# DDR4_SODIMM_Arria10.net
KiCad netlist of a schematic drawn in Altium Designer
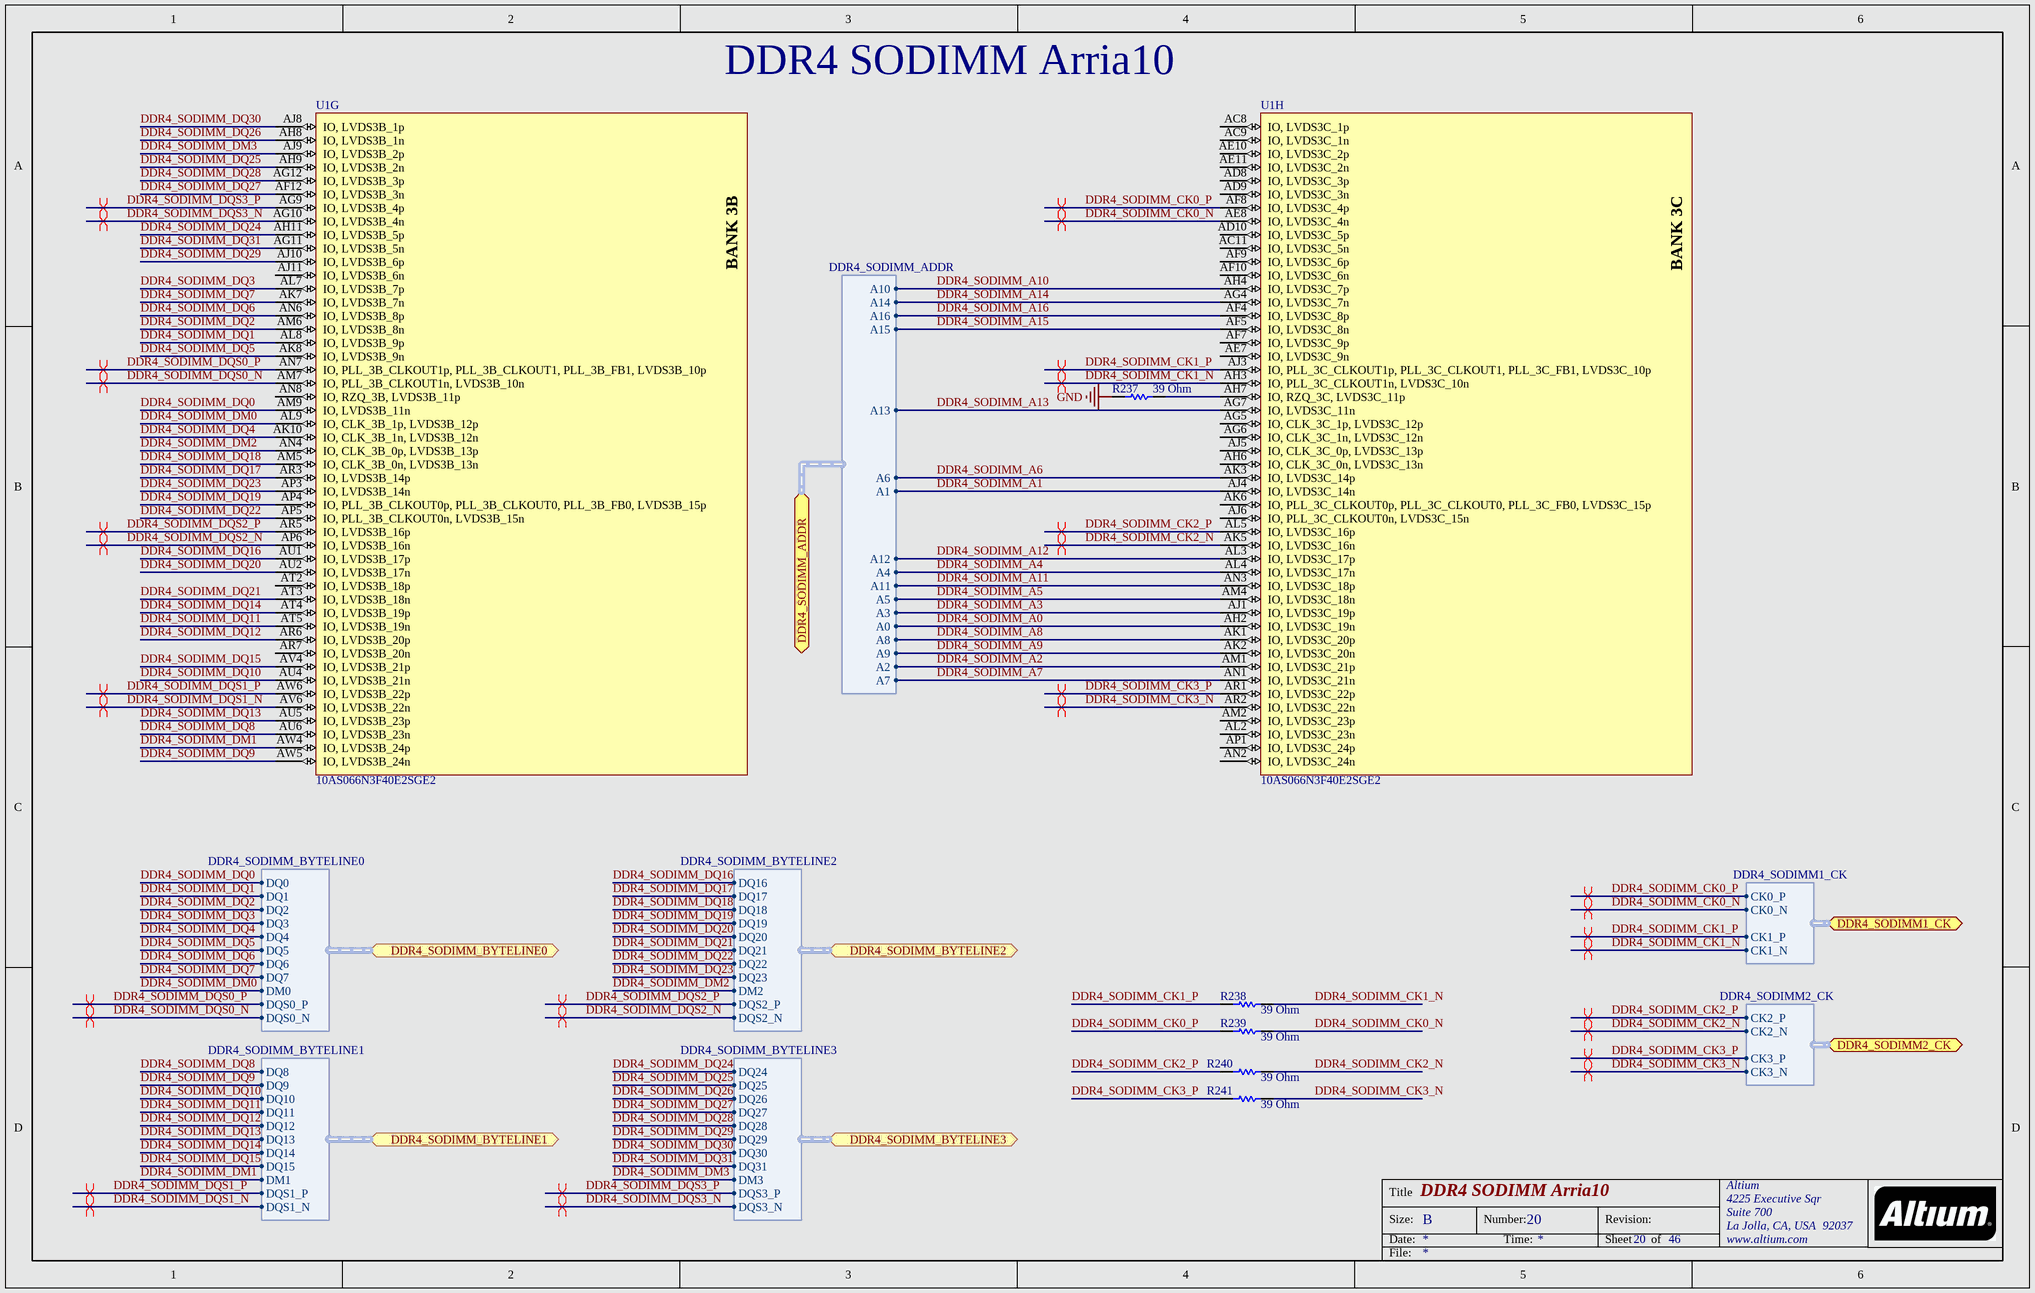
[diagram p0: DDR4_SODIMM_Arria10.SchDoc]

(export (version "E")
  (design (tool "Eeschema 10.0.6"))
  (components
    (comp (ref "R237")
      (value "RC0402JR-0739RL")
      (footprint "RESC1005X40X25NL5T10")
      (description "Chip Resistor, 39 Ohm, +/- 5%, 0.063 W, -55 to 155 degC, 0402 (1005 Metric), RoHS, Tape and Reel")
      (fields (field (name "TOLERANCE") "5%") (field (name "RESISTANCE") "39 Ohm"))
      (libsource (lib "Altium Content Vault") (part "CMP-2002-07994-2"))
    )
    (comp (ref "R238")
      (value "RC0402JR-0739RL")
      (footprint "RESC1005X40X25NL5T10")
      (description "Chip Resistor, 39 Ohm, +/- 5%, 0.063 W, -55 to 155 degC, 0402 (1005 Metric), RoHS, Tape and Reel")
      (fields (field (name "TOLERANCE") "5%") (field (name "RESISTANCE") "39 Ohm"))
      (libsource (lib "Altium Content Vault") (part "CMP-2002-07994-2"))
    )
    (comp (ref "R239")
      (value "RC0402JR-0739RL")
      (footprint "RESC1005X40X25NL5T10")
      (description "Chip Resistor, 39 Ohm, +/- 5%, 0.063 W, -55 to 155 degC, 0402 (1005 Metric), RoHS, Tape and Reel")
      (fields (field (name "TOLERANCE") "5%") (field (name "RESISTANCE") "39 Ohm"))
      (libsource (lib "Altium Content Vault") (part "CMP-2002-07994-2"))
    )
    (comp (ref "R240")
      (value "RC0402JR-0739RL")
      (footprint "RESC1005X40X25NL5T10")
      (description "Chip Resistor, 39 Ohm, +/- 5%, 0.063 W, -55 to 155 degC, 0402 (1005 Metric), RoHS, Tape and Reel")
      (fields (field (name "TOLERANCE") "5%") (field (name "RESISTANCE") "39 Ohm"))
      (libsource (lib "Altium Content Vault") (part "CMP-2002-07994-2"))
    )
    (comp (ref "R241")
      (value "RC0402JR-0739RL")
      (footprint "RESC1005X40X25NL5T10")
      (description "Chip Resistor, 39 Ohm, +/- 5%, 0.063 W, -55 to 155 degC, 0402 (1005 Metric), RoHS, Tape and Reel")
      (fields (field (name "TOLERANCE") "5%") (field (name "RESISTANCE") "39 Ohm"))
      (libsource (lib "Altium Content Vault") (part "CMP-2002-07994-2"))
    )
    (comp (ref "U1")
      (value "10AS066N3F40E2SGE2")
      (footprint "ALTR-FBGA1517_A-350")
      (libsource (lib "Altium Content Vault") (part "ALTR-10AS066NF40-FBGA1517"))
    )
  )
  (nets
    (net (code "8") (name "/DDR4_SODIMM_A0") (class "Default")
      (node (ref "U1") (pin "AH2") (pinfunction "IO,_LVDS3C_19n_AH2") (pintype "bidirectional"))
    )
    (net (code "9") (name "/DDR4_SODIMM_A1") (class "Default")
      (node (ref "U1") (pin "AJ4") (pinfunction "IO,_LVDS3C_14n_AJ4") (pintype "bidirectional"))
    )
    (net (code "10") (name "/DDR4_SODIMM_A2") (class "Default")
      (node (ref "U1") (pin "AM1") (pinfunction "IO,_LVDS3C_21p_AM1") (pintype "bidirectional"))
    )
    (net (code "11") (name "/DDR4_SODIMM_A3") (class "Default")
      (node (ref "U1") (pin "AJ1") (pinfunction "IO,_LVDS3C_19p_AJ1") (pintype "bidirectional"))
    )
    (net (code "12") (name "/DDR4_SODIMM_A4") (class "Default")
      (node (ref "U1") (pin "AL4") (pinfunction "IO,_LVDS3C_17n_AL4") (pintype "bidirectional"))
    )
    (net (code "13") (name "/DDR4_SODIMM_A5") (class "Default")
      (node (ref "U1") (pin "AM4") (pinfunction "IO,_LVDS3C_18n_AM4") (pintype "bidirectional"))
    )
    (net (code "14") (name "/DDR4_SODIMM_A6") (class "Default")
      (node (ref "U1") (pin "AK3") (pinfunction "IO,_LVDS3C_14p_AK3") (pintype "bidirectional"))
    )
    (net (code "15") (name "/DDR4_SODIMM_A7") (class "Default")
      (node (ref "U1") (pin "AN1") (pinfunction "IO,_LVDS3C_21n_AN1") (pintype "bidirectional"))
    )
    (net (code "16") (name "/DDR4_SODIMM_A8") (class "Default")
      (node (ref "U1") (pin "AK1") (pinfunction "IO,_LVDS3C_20p_AK1") (pintype "bidirectional"))
    )
    (net (code "17") (name "/DDR4_SODIMM_A9") (class "Default")
      (node (ref "U1") (pin "AK2") (pinfunction "IO,_LVDS3C_20n_AK2") (pintype "bidirectional"))
    )
    (net (code "18") (name "/DDR4_SODIMM_A10") (class "Default")
      (node (ref "U1") (pin "AH4") (pinfunction "IO,_LVDS3C_7p_AH4") (pintype "bidirectional"))
    )
    (net (code "19") (name "/DDR4_SODIMM_A11") (class "Default")
      (node (ref "U1") (pin "AN3") (pinfunction "IO,_LVDS3C_18p_AN3") (pintype "bidirectional"))
    )
    (net (code "20") (name "/DDR4_SODIMM_A12") (class "Default")
      (node (ref "U1") (pin "AL3") (pinfunction "IO,_LVDS3C_17p_AL3") (pintype "bidirectional"))
    )
    (net (code "21") (name "/DDR4_SODIMM_A13") (class "Default")
      (node (ref "U1") (pin "AG7") (pinfunction "IO,_LVDS3C_11n_AG7") (pintype "bidirectional"))
    )
    (net (code "22") (name "/DDR4_SODIMM_A14") (class "Default")
      (node (ref "U1") (pin "AG4") (pinfunction "IO,_LVDS3C_7n_AG4") (pintype "bidirectional"))
    )
    (net (code "23") (name "/DDR4_SODIMM_A15") (class "Default")
      (node (ref "U1") (pin "AF5") (pinfunction "IO,_LVDS3C_8n_AF5") (pintype "bidirectional"))
    )
    (net (code "24") (name "/DDR4_SODIMM_A16") (class "Default")
      (node (ref "U1") (pin "AF4") (pinfunction "IO,_LVDS3C_8p_AF4") (pintype "bidirectional"))
    )
    (net (code "25") (name "/DDR4_SODIMM_CK0_N") (class "Default")
      (node (ref "R239") (pin "2") (pinfunction "2_2") (pintype "passive"))
      (node (ref "U1") (pin "AE8") (pinfunction "IO,_LVDS3C_4n_AE8") (pintype "bidirectional"))
    )
    (net (code "26") (name "/DDR4_SODIMM_CK0_P") (class "Default")
      (node (ref "R239") (pin "1") (pinfunction "1_1") (pintype "passive"))
      (node (ref "U1") (pin "AF8") (pinfunction "IO,_LVDS3C_4p_AF8") (pintype "bidirectional"))
    )
    (net (code "27") (name "/DDR4_SODIMM_CK1_N") (class "Default")
      (node (ref "R238") (pin "2") (pinfunction "2_2") (pintype "passive"))
      (node (ref "U1") (pin "AH3") (pinfunction "IO,_PLL_3C_CLKOUT1n,_LVDS3C_10n_AH3") (pintype "bidirectional"))
    )
    (net (code "28") (name "/DDR4_SODIMM_CK1_P") (class "Default")
      (node (ref "R238") (pin "1") (pinfunction "1_1") (pintype "passive"))
      (node (ref "U1") (pin "AJ3") (pinfunction "IO,_PLL_3C_CLKOUT1p,_PLL_3C_CLKOUT1,_PLL_3C_FB1,_LVDS3C_10p_AJ3") (pintype "bidirectional"))
    )
    (net (code "29") (name "/DDR4_SODIMM_CK2_N") (class "Default")
      (node (ref "R240") (pin "2") (pinfunction "2_2") (pintype "passive"))
      (node (ref "U1") (pin "AK5") (pinfunction "IO,_LVDS3C_16n_AK5") (pintype "bidirectional"))
    )
    (net (code "30") (name "/DDR4_SODIMM_CK2_P") (class "Default")
      (node (ref "R240") (pin "1") (pinfunction "1_1") (pintype "passive"))
      (node (ref "U1") (pin "AL5") (pinfunction "IO,_LVDS3C_16p_AL5") (pintype "bidirectional"))
    )
    (net (code "31") (name "/DDR4_SODIMM_CK3_N") (class "Default")
      (node (ref "R241") (pin "2") (pinfunction "2_2") (pintype "passive"))
      (node (ref "U1") (pin "AR2") (pinfunction "IO,_LVDS3C_22n_AR2") (pintype "bidirectional"))
    )
    (net (code "32") (name "/DDR4_SODIMM_CK3_P") (class "Default")
      (node (ref "R241") (pin "1") (pinfunction "1_1") (pintype "passive"))
      (node (ref "U1") (pin "AR1") (pinfunction "IO,_LVDS3C_22p_AR1") (pintype "bidirectional"))
    )
    (net (code "33") (name "/DDR4_SODIMM_DM0") (class "Default")
      (node (ref "U1") (pin "AL9") (pinfunction "IO,_CLK_3B_1p,_LVDS3B_12p_AL9") (pintype "bidirectional"))
    )
    (net (code "34") (name "/DDR4_SODIMM_DM1") (class "Default")
      (node (ref "U1") (pin "AW4") (pinfunction "IO,_LVDS3B_24p_AW4") (pintype "bidirectional"))
    )
    (net (code "35") (name "/DDR4_SODIMM_DM2") (class "Default")
      (node (ref "U1") (pin "AN4") (pinfunction "IO,_CLK_3B_0p,_LVDS3B_13p_AN4") (pintype "bidirectional"))
    )
    (net (code "36") (name "/DDR4_SODIMM_DM3") (class "Default")
      (node (ref "U1") (pin "AJ9") (pinfunction "IO,_LVDS3B_2p_AJ9") (pintype "bidirectional"))
    )
    (net (code "37") (name "/DDR4_SODIMM_DQ0") (class "Default")
      (node (ref "U1") (pin "AM9") (pinfunction "IO,_LVDS3B_11n_AM9") (pintype "bidirectional"))
    )
    (net (code "38") (name "/DDR4_SODIMM_DQ1") (class "Default")
      (node (ref "U1") (pin "AL8") (pinfunction "IO,_LVDS3B_9p_AL8") (pintype "bidirectional"))
    )
    (net (code "39") (name "/DDR4_SODIMM_DQ2") (class "Default")
      (node (ref "U1") (pin "AM6") (pinfunction "IO,_LVDS3B_8n_AM6") (pintype "bidirectional"))
    )
    (net (code "40") (name "/DDR4_SODIMM_DQ3") (class "Default")
      (node (ref "U1") (pin "AL7") (pinfunction "IO,_LVDS3B_7p_AL7") (pintype "bidirectional"))
    )
    (net (code "41") (name "/DDR4_SODIMM_DQ4") (class "Default")
      (node (ref "U1") (pin "AK10") (pinfunction "IO,_CLK_3B_1n,_LVDS3B_12n_AK10") (pintype "bidirectional"))
    )
    (net (code "42") (name "/DDR4_SODIMM_DQ5") (class "Default")
      (node (ref "U1") (pin "AK8") (pinfunction "IO,_LVDS3B_9n_AK8") (pintype "bidirectional"))
    )
    (net (code "43") (name "/DDR4_SODIMM_DQ6") (class "Default")
      (node (ref "U1") (pin "AN6") (pinfunction "IO,_LVDS3B_8p_AN6") (pintype "bidirectional"))
    )
    (net (code "44") (name "/DDR4_SODIMM_DQ7") (class "Default")
      (node (ref "U1") (pin "AK7") (pinfunction "IO,_LVDS3B_7n_AK7") (pintype "bidirectional"))
    )
    (net (code "45") (name "/DDR4_SODIMM_DQ8") (class "Default")
      (node (ref "U1") (pin "AU6") (pinfunction "IO,_LVDS3B_23n_AU6") (pintype "bidirectional"))
    )
    (net (code "46") (name "/DDR4_SODIMM_DQ9") (class "Default")
      (node (ref "U1") (pin "AW5") (pinfunction "IO,_LVDS3B_24n_AW5") (pintype "bidirectional"))
    )
    (net (code "47") (name "/DDR4_SODIMM_DQ10") (class "Default")
      (node (ref "U1") (pin "AU4") (pinfunction "IO,_LVDS3B_21n_AU4") (pintype "bidirectional"))
    )
    (net (code "48") (name "/DDR4_SODIMM_DQ11") (class "Default")
      (node (ref "U1") (pin "AT5") (pinfunction "IO,_LVDS3B_19n_AT5") (pintype "bidirectional"))
    )
    (net (code "49") (name "/DDR4_SODIMM_DQ12") (class "Default")
      (node (ref "U1") (pin "AR6") (pinfunction "IO,_LVDS3B_20p_AR6") (pintype "bidirectional"))
    )
    (net (code "50") (name "/DDR4_SODIMM_DQ13") (class "Default")
      (node (ref "U1") (pin "AU5") (pinfunction "IO,_LVDS3B_23p_AU5") (pintype "bidirectional"))
    )
    (net (code "51") (name "/DDR4_SODIMM_DQ14") (class "Default")
      (node (ref "U1") (pin "AT4") (pinfunction "IO,_LVDS3B_19p_AT4") (pintype "bidirectional"))
    )
    (net (code "52") (name "/DDR4_SODIMM_DQ15") (class "Default")
      (node (ref "U1") (pin "AV4") (pinfunction "IO,_LVDS3B_21p_AV4") (pintype "bidirectional"))
    )
    (net (code "53") (name "/DDR4_SODIMM_DQ16") (class "Default")
      (node (ref "U1") (pin "AU1") (pinfunction "IO,_LVDS3B_17p_AU1") (pintype "bidirectional"))
    )
    (net (code "54") (name "/DDR4_SODIMM_DQ17") (class "Default")
      (node (ref "U1") (pin "AR3") (pinfunction "IO,_LVDS3B_14p_AR3") (pintype "bidirectional"))
    )
    (net (code "55") (name "/DDR4_SODIMM_DQ18") (class "Default")
      (node (ref "U1") (pin "AM5") (pinfunction "IO,_CLK_3B_0n,_LVDS3B_13n_AM5") (pintype "bidirectional"))
    )
    (net (code "56") (name "/DDR4_SODIMM_DQ19") (class "Default")
      (node (ref "U1") (pin "AP4") (pinfunction "IO,_PLL_3B_CLKOUT0p,_PLL_3B_CLKOUT0,_PLL_3B_FB0,_LVDS3B_15p_AP4") (pintype "bidirectional"))
    )
    (net (code "57") (name "/DDR4_SODIMM_DQ20") (class "Default")
      (node (ref "U1") (pin "AU2") (pinfunction "IO,_LVDS3B_17n_AU2") (pintype "bidirectional"))
    )
    (net (code "58") (name "/DDR4_SODIMM_DQ21") (class "Default")
      (node (ref "U1") (pin "AT3") (pinfunction "IO,_LVDS3B_18n_AT3") (pintype "bidirectional"))
    )
    (net (code "59") (name "/DDR4_SODIMM_DQ22") (class "Default")
      (node (ref "U1") (pin "AP5") (pinfunction "IO,_PLL_3B_CLKOUT0n,_LVDS3B_15n_AP5") (pintype "bidirectional"))
    )
    (net (code "60") (name "/DDR4_SODIMM_DQ23") (class "Default")
      (node (ref "U1") (pin "AP3") (pinfunction "IO,_LVDS3B_14n_AP3") (pintype "bidirectional"))
    )
    (net (code "61") (name "/DDR4_SODIMM_DQ24") (class "Default")
      (node (ref "U1") (pin "AH11") (pinfunction "IO,_LVDS3B_5p_AH11") (pintype "bidirectional"))
    )
    (net (code "62") (name "/DDR4_SODIMM_DQ25") (class "Default")
      (node (ref "U1") (pin "AH9") (pinfunction "IO,_LVDS3B_2n_AH9") (pintype "bidirectional"))
    )
    (net (code "63") (name "/DDR4_SODIMM_DQ26") (class "Default")
      (node (ref "U1") (pin "AH8") (pinfunction "IO,_LVDS3B_1n_AH8") (pintype "bidirectional"))
    )
    (net (code "64") (name "/DDR4_SODIMM_DQ27") (class "Default")
      (node (ref "U1") (pin "AF12") (pinfunction "IO,_LVDS3B_3n_AF12") (pintype "bidirectional"))
    )
    (net (code "65") (name "/DDR4_SODIMM_DQ28") (class "Default")
      (node (ref "U1") (pin "AG12") (pinfunction "IO,_LVDS3B_3p_AG12") (pintype "bidirectional"))
    )
    (net (code "66") (name "/DDR4_SODIMM_DQ29") (class "Default")
      (node (ref "U1") (pin "AJ10") (pinfunction "IO,_LVDS3B_6p_AJ10") (pintype "bidirectional"))
    )
    (net (code "67") (name "/DDR4_SODIMM_DQ30") (class "Default")
      (node (ref "U1") (pin "AJ8") (pinfunction "IO,_LVDS3B_1p_AJ8") (pintype "bidirectional"))
    )
    (net (code "68") (name "/DDR4_SODIMM_DQ31") (class "Default")
      (node (ref "U1") (pin "AG11") (pinfunction "IO,_LVDS3B_5n_AG11") (pintype "bidirectional"))
    )
    (net (code "69") (name "/DDR4_SODIMM_DQS0_N") (class "Default")
      (node (ref "U1") (pin "AM7") (pinfunction "IO,_PLL_3B_CLKOUT1n,_LVDS3B_10n_AM7") (pintype "bidirectional"))
    )
    (net (code "70") (name "/DDR4_SODIMM_DQS0_P") (class "Default")
      (node (ref "U1") (pin "AN7") (pinfunction "IO,_PLL_3B_CLKOUT1p,_PLL_3B_CLKOUT1,_PLL_3B_FB1,_LVDS3B_10p_AN7") (pintype "bidirectional"))
    )
    (net (code "71") (name "/DDR4_SODIMM_DQS1_N") (class "Default")
      (node (ref "U1") (pin "AV6") (pinfunction "IO,_LVDS3B_22n_AV6") (pintype "bidirectional"))
    )
    (net (code "72") (name "/DDR4_SODIMM_DQS1_P") (class "Default")
      (node (ref "U1") (pin "AW6") (pinfunction "IO,_LVDS3B_22p_AW6") (pintype "bidirectional"))
    )
    (net (code "73") (name "/DDR4_SODIMM_DQS2_N") (class "Default")
      (node (ref "U1") (pin "AP6") (pinfunction "IO,_LVDS3B_16n_AP6") (pintype "bidirectional"))
    )
    (net (code "74") (name "/DDR4_SODIMM_DQS2_P") (class "Default")
      (node (ref "U1") (pin "AR5") (pinfunction "IO,_LVDS3B_16p_AR5") (pintype "bidirectional"))
    )
    (net (code "75") (name "/DDR4_SODIMM_DQS3_N") (class "Default")
      (node (ref "U1") (pin "AG10") (pinfunction "IO,_LVDS3B_4n_AG10") (pintype "bidirectional"))
    )
    (net (code "76") (name "/DDR4_SODIMM_DQS3_P") (class "Default")
      (node (ref "U1") (pin "AG9") (pinfunction "IO,_LVDS3B_4p_AG9") (pintype "bidirectional"))
    )
    (net (code "84") (name "GND") (class "Default")
      (node (ref "R237") (pin "1") (pinfunction "1_1") (pintype "passive"))
    )
    (net (code "85") (name "Net-(U1H-IO,_RZQ_3C,_LVDS3C_11p)") (class "Default")
      (node (ref "R237") (pin "2") (pinfunction "2_2") (pintype "passive"))
      (node (ref "U1") (pin "AH7") (pinfunction "IO,_RZQ_3C,_LVDS3C_11p_AH7") (pintype "bidirectional"))
    )
    (net (code "86") (name "unconnected-(U1G-IO,_LVDS3B_6n-PadAJ11)") (class "Default")
      (node (ref "U1") (pin "AJ11") (pinfunction "IO,_LVDS3B_6n_AJ11") (pintype "bidirectional"))
    )
    (net (code "87") (name "unconnected-(U1G-IO,_LVDS3B_18p-PadAT2)") (class "Default")
      (node (ref "U1") (pin "AT2") (pinfunction "IO,_LVDS3B_18p_AT2") (pintype "bidirectional"))
    )
    (net (code "88") (name "unconnected-(U1G-IO,_LVDS3B_20n-PadAR7)") (class "Default")
      (node (ref "U1") (pin "AR7") (pinfunction "IO,_LVDS3B_20n_AR7") (pintype "bidirectional"))
    )
    (net (code "89") (name "unconnected-(U1G-IO,_RZQ_3B,_LVDS3B_11p-PadAN8)") (class "Default")
      (node (ref "U1") (pin "AN8") (pinfunction "IO,_RZQ_3B,_LVDS3B_11p_AN8") (pintype "bidirectional"))
    )
    (net (code "90") (name "unconnected-(U1H-IO,_CLK_3C_0n,_LVDS3C_13n-PadAH6)") (class "Default")
      (node (ref "U1") (pin "AH6") (pinfunction "IO,_CLK_3C_0n,_LVDS3C_13n_AH6") (pintype "bidirectional"))
    )
    (net (code "91") (name "unconnected-(U1H-IO,_CLK_3C_0p,_LVDS3C_13p-PadAJ5)") (class "Default")
      (node (ref "U1") (pin "AJ5") (pinfunction "IO,_CLK_3C_0p,_LVDS3C_13p_AJ5") (pintype "bidirectional"))
    )
    (net (code "92") (name "unconnected-(U1H-IO,_CLK_3C_1n,_LVDS3C_12n-PadAG6)") (class "Default")
      (node (ref "U1") (pin "AG6") (pinfunction "IO,_CLK_3C_1n,_LVDS3C_12n_AG6") (pintype "bidirectional"))
    )
    (net (code "93") (name "unconnected-(U1H-IO,_CLK_3C_1p,_LVDS3C_12p-PadAG5)") (class "Default")
      (node (ref "U1") (pin "AG5") (pinfunction "IO,_CLK_3C_1p,_LVDS3C_12p_AG5") (pintype "bidirectional"))
    )
    (net (code "94") (name "unconnected-(U1H-IO,_LVDS3C_1n-PadAC9)") (class "Default")
      (node (ref "U1") (pin "AC9") (pinfunction "IO,_LVDS3C_1n_AC9") (pintype "bidirectional"))
    )
    (net (code "95") (name "unconnected-(U1H-IO,_LVDS3C_1p-PadAC8)") (class "Default")
      (node (ref "U1") (pin "AC8") (pinfunction "IO,_LVDS3C_1p_AC8") (pintype "bidirectional"))
    )
    (net (code "96") (name "unconnected-(U1H-IO,_LVDS3C_2n-PadAE11)") (class "Default")
      (node (ref "U1") (pin "AE11") (pinfunction "IO,_LVDS3C_2n_AE11") (pintype "bidirectional"))
    )
    (net (code "97") (name "unconnected-(U1H-IO,_LVDS3C_2p-PadAE10)") (class "Default")
      (node (ref "U1") (pin "AE10") (pinfunction "IO,_LVDS3C_2p_AE10") (pintype "bidirectional"))
    )
    (net (code "98") (name "unconnected-(U1H-IO,_LVDS3C_3n-PadAD9)") (class "Default")
      (node (ref "U1") (pin "AD9") (pinfunction "IO,_LVDS3C_3n_AD9") (pintype "bidirectional"))
    )
    (net (code "99") (name "unconnected-(U1H-IO,_LVDS3C_3p-PadAD8)") (class "Default")
      (node (ref "U1") (pin "AD8") (pinfunction "IO,_LVDS3C_3p_AD8") (pintype "bidirectional"))
    )
    (net (code "100") (name "unconnected-(U1H-IO,_LVDS3C_5n-PadAC11)") (class "Default")
      (node (ref "U1") (pin "AC11") (pinfunction "IO,_LVDS3C_5n_AC11") (pintype "bidirectional"))
    )
    (net (code "101") (name "unconnected-(U1H-IO,_LVDS3C_5p-PadAD10)") (class "Default")
      (node (ref "U1") (pin "AD10") (pinfunction "IO,_LVDS3C_5p_AD10") (pintype "bidirectional"))
    )
    (net (code "102") (name "unconnected-(U1H-IO,_LVDS3C_6n-PadAF10)") (class "Default")
      (node (ref "U1") (pin "AF10") (pinfunction "IO,_LVDS3C_6n_AF10") (pintype "bidirectional"))
    )
    (net (code "103") (name "unconnected-(U1H-IO,_LVDS3C_6p-PadAF9)") (class "Default")
      (node (ref "U1") (pin "AF9") (pinfunction "IO,_LVDS3C_6p_AF9") (pintype "bidirectional"))
    )
    (net (code "104") (name "unconnected-(U1H-IO,_LVDS3C_9n-PadAE7)") (class "Default")
      (node (ref "U1") (pin "AE7") (pinfunction "IO,_LVDS3C_9n_AE7") (pintype "bidirectional"))
    )
    (net (code "105") (name "unconnected-(U1H-IO,_LVDS3C_9p-PadAF7)") (class "Default")
      (node (ref "U1") (pin "AF7") (pinfunction "IO,_LVDS3C_9p_AF7") (pintype "bidirectional"))
    )
    (net (code "106") (name "unconnected-(U1H-IO,_LVDS3C_23n-PadAL2)") (class "Default")
      (node (ref "U1") (pin "AL2") (pinfunction "IO,_LVDS3C_23n_AL2") (pintype "bidirectional"))
    )
    (net (code "107") (name "unconnected-(U1H-IO,_LVDS3C_23p-PadAM2)") (class "Default")
      (node (ref "U1") (pin "AM2") (pinfunction "IO,_LVDS3C_23p_AM2") (pintype "bidirectional"))
    )
    (net (code "108") (name "unconnected-(U1H-IO,_LVDS3C_24n-PadAN2)") (class "Default")
      (node (ref "U1") (pin "AN2") (pinfunction "IO,_LVDS3C_24n_AN2") (pintype "bidirectional"))
    )
    (net (code "109") (name "unconnected-(U1H-IO,_LVDS3C_24p-PadAP1)") (class "Default")
      (node (ref "U1") (pin "AP1") (pinfunction "IO,_LVDS3C_24p_AP1") (pintype "bidirectional"))
    )
    (net (code "110") (name "unconnected-(U1H-IO,_PLL_3C_CLKOUT0n,_LVDS3C_15n-PadAJ6)") (class "Default")
      (node (ref "U1") (pin "AJ6") (pinfunction "IO,_PLL_3C_CLKOUT0n,_LVDS3C_15n_AJ6") (pintype "bidirectional"))
    )
    (net (code "111") (name "unconnected-(U1H-IO,_PLL_3C_CLKOUT0p,_PLL_3C_CLKOUT0,_PLL_3C_FB0,_LVDS3C_15p-PadAK6)") (class "Default")
      (node (ref "U1") (pin "AK6") (pinfunction "IO,_PLL_3C_CLKOUT0p,_PLL_3C_CLKOUT0,_PLL_3C_FB0,_LVDS3C_15p_AK6") (pintype "bidirectional"))
    )
  )
)
